# FitnessTracker.net
KiCad netlist of a schematic drawn in EAGLE
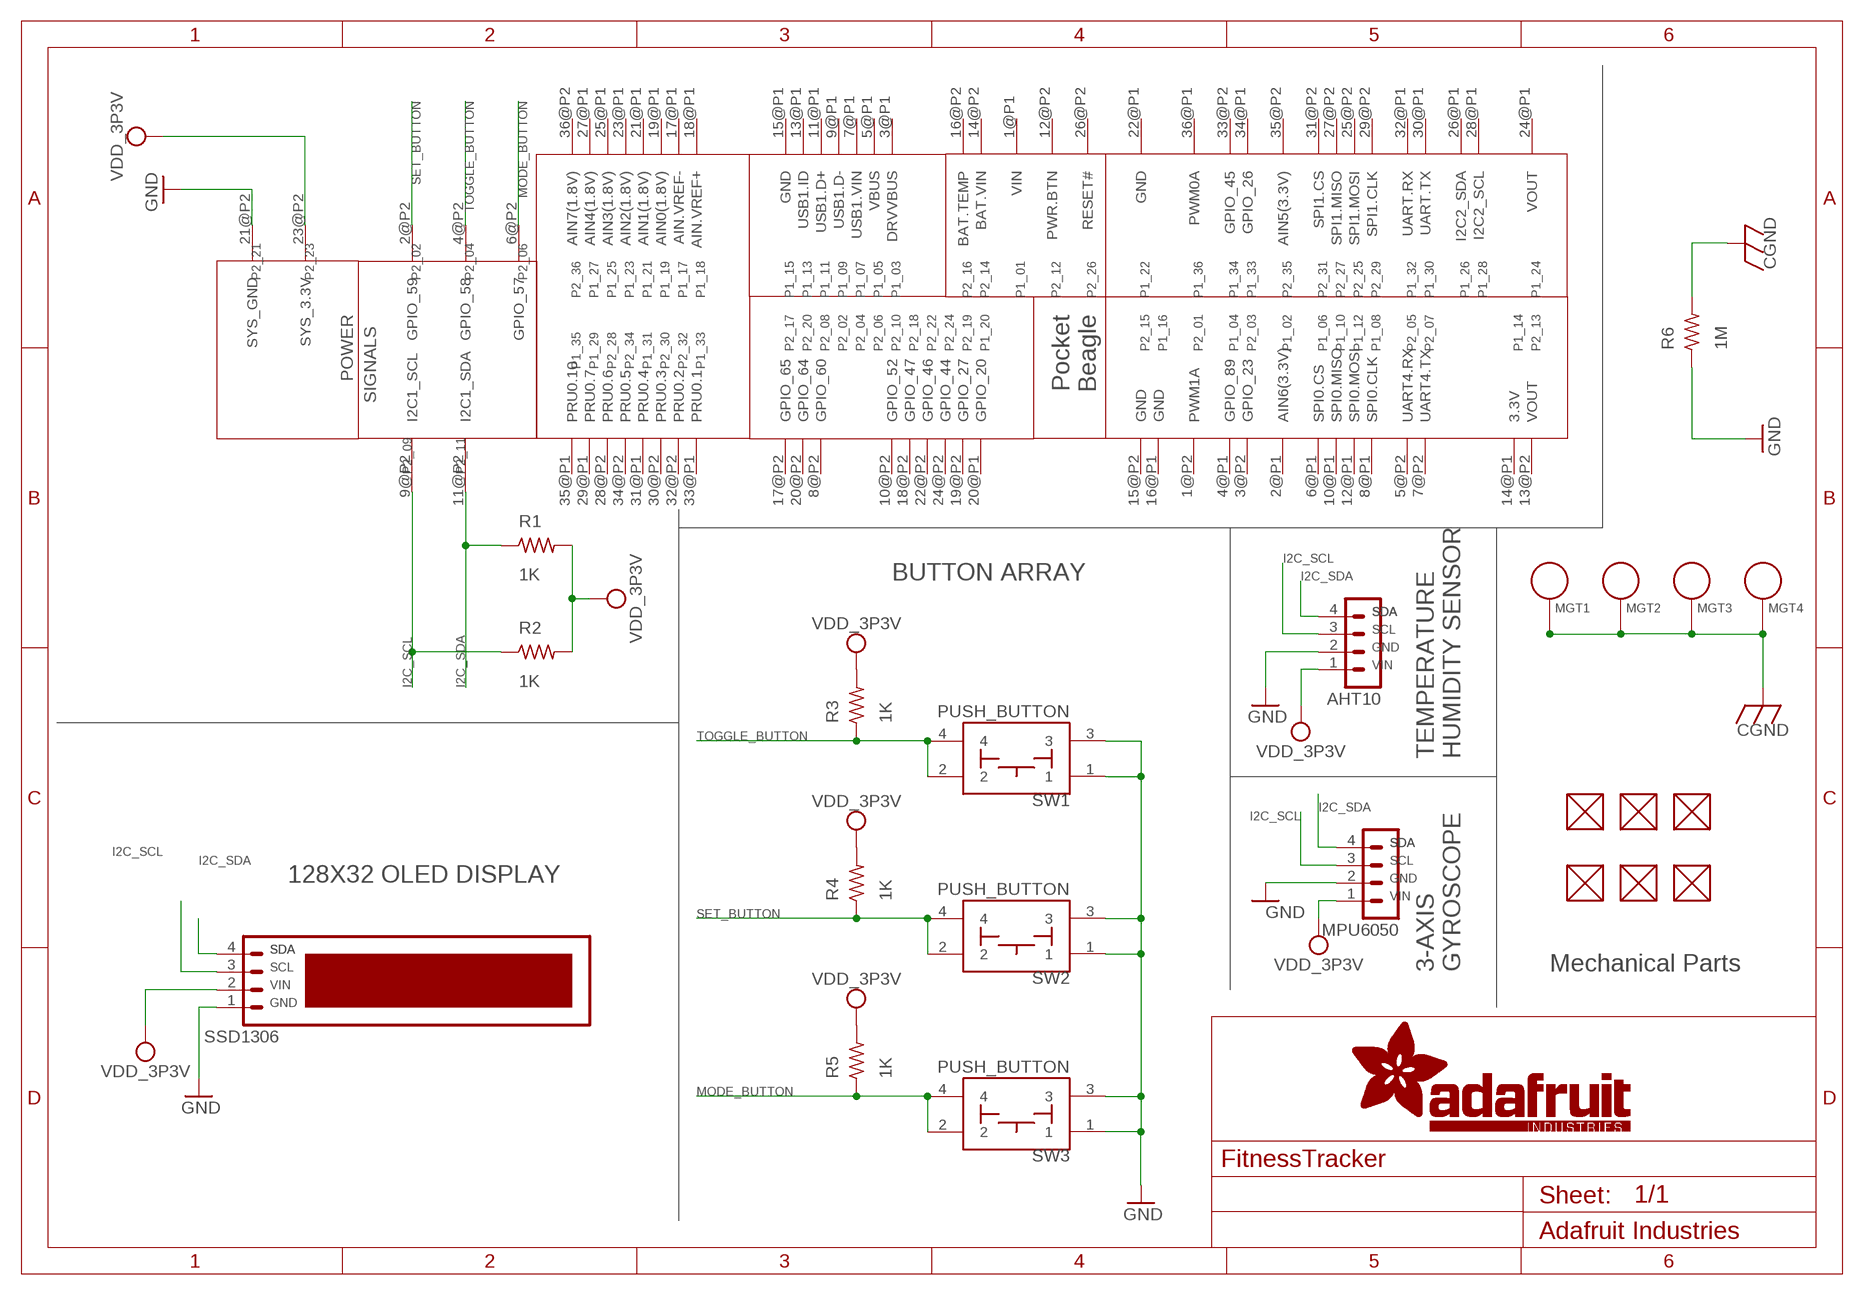
[diagram p0: schematic, sheet 1]

(export (version "E")
  (design (tool "Eeschema 10.0.6"))
  (components
    (comp (ref "FUD1")
      (value "FIDUCIAL")
      (footprint "eagle-import:FIDUCIAL_40MIL")
      (libsource (lib "eagle-import") (part "FIDUCIAL"))
    )
    (comp (ref "FUD2")
      (value "FIDUCIAL")
      (footprint "eagle-import:FIDUCIAL_40MIL")
      (libsource (lib "eagle-import") (part "FIDUCIAL"))
    )
    (comp (ref "FUD3")
      (value "FIDUCIAL")
      (footprint "eagle-import:FIDUCIAL_40MIL")
      (libsource (lib "eagle-import") (part "FIDUCIAL"))
    )
    (comp (ref "FUD4")
      (value "FIDUCIAL")
      (footprint "eagle-import:FIDUCIAL_40MIL")
      (libsource (lib "eagle-import") (part "FIDUCIAL"))
    )
    (comp (ref "FUD5")
      (value "FIDUCIAL")
      (footprint "eagle-import:FIDUCIAL_40MIL")
      (libsource (lib "eagle-import") (part "FIDUCIAL"))
    )
    (comp (ref "FUD6")
      (value "FIDUCIAL")
      (footprint "eagle-import:FIDUCIAL_40MIL")
      (libsource (lib "eagle-import") (part "FIDUCIAL"))
    )
    (comp (ref "MGT1")
      (value "MOUNTING_HOLE")
      (footprint "eagle-import:MOUNTING_HOLE")
      (libsource (lib "eagle-import") (part "MOUNTING_HOLE"))
    )
    (comp (ref "MGT2")
      (value "MOUNTING_HOLE")
      (footprint "eagle-import:MOUNTING_HOLE")
      (libsource (lib "eagle-import") (part "MOUNTING_HOLE"))
    )
    (comp (ref "MGT3")
      (value "MOUNTING_HOLE")
      (footprint "eagle-import:MOUNTING_HOLE")
      (libsource (lib "eagle-import") (part "MOUNTING_HOLE"))
    )
    (comp (ref "MGT4")
      (value "MOUNTING_HOLE")
      (footprint "eagle-import:MOUNTING_HOLE")
      (libsource (lib "eagle-import") (part "MOUNTING_HOLE"))
    )
    (comp (ref "R1")
      (value "1K")
      (footprint "eagle-import:R0603")
      (libsource (lib "eagle-import") (part "R_R0603"))
    )
    (comp (ref "R2")
      (value "1K")
      (footprint "eagle-import:R0603")
      (libsource (lib "eagle-import") (part "R_R0603"))
    )
    (comp (ref "R3")
      (value "1K")
      (footprint "eagle-import:R0603")
      (libsource (lib "eagle-import") (part "R_R0603"))
    )
    (comp (ref "R4")
      (value "1K")
      (footprint "eagle-import:R0603")
      (libsource (lib "eagle-import") (part "R_R0603"))
    )
    (comp (ref "R5")
      (value "1K")
      (footprint "eagle-import:R0603")
      (libsource (lib "eagle-import") (part "R_R0603"))
    )
    (comp (ref "R6")
      (value "1M")
      (footprint "eagle-import:R0603")
      (libsource (lib "eagle-import") (part "R_R0603"))
    )
    (comp (ref "SW1")
      (value "PUSH_BUTTON")
      (footprint "eagle-import:BUTTON_12.5MM")
      (libsource (lib "eagle-import") (part "PUSH_BUTTON"))
    )
    (comp (ref "SW2")
      (value "PUSH_BUTTON")
      (footprint "eagle-import:BUTTON_12.5MM")
      (libsource (lib "eagle-import") (part "PUSH_BUTTON"))
    )
    (comp (ref "SW3")
      (value "PUSH_BUTTON")
      (footprint "eagle-import:BUTTON_12.5MM")
      (libsource (lib "eagle-import") (part "PUSH_BUTTON"))
    )
    (comp (ref "U$1")
      (value "POCKETBEAGLE")
      (footprint "eagle-import:POCKETBEAGLE")
      (libsource (lib "eagle-import") (part "POCKETBEAGLE"))
    )
    (comp (ref "U$2")
      (value "SSD1306")
      (footprint "eagle-import:MA04-1")
      (libsource (lib "eagle-import") (part "SSD1306"))
    )
    (comp (ref "U$3")
      (value "MPU6050")
      (footprint "eagle-import:MA04-1")
      (libsource (lib "eagle-import") (part "MPU6050"))
    )
    (comp (ref "U$4")
      (value "AHT10")
      (footprint "eagle-import:MA04-1")
      (libsource (lib "eagle-import") (part "AHT10"))
    )
  )
  (nets
    (net (code "1") (name "/I2C_SCL") (class "Default")
      (node (ref "R2") (pin "1") (pinfunction "1_1") (pintype "passive"))
      (node (ref "U$1") (pin "9@P2") (pinfunction "I2C1_SCL_9@P2") (pintype "bidirectional"))
      (node (ref "U$2") (pin "3") (pinfunction "SCL_3") (pintype "passive"))
      (node (ref "U$3") (pin "3") (pinfunction "SCL_3") (pintype "passive"))
      (node (ref "U$4") (pin "3") (pinfunction "SCL_3") (pintype "passive"))
    )
    (net (code "2") (name "/I2C_SDA") (class "Default")
      (node (ref "R1") (pin "1") (pinfunction "1_1") (pintype "passive"))
      (node (ref "U$1") (pin "11@P2") (pinfunction "I2C1_SDA_11@P2") (pintype "bidirectional"))
      (node (ref "U$2") (pin "4") (pinfunction "SDA_4") (pintype "passive"))
      (node (ref "U$3") (pin "4") (pinfunction "SDA_4") (pintype "passive"))
      (node (ref "U$4") (pin "4") (pinfunction "SDA_4") (pintype "passive"))
    )
    (net (code "3") (name "/MODE_BUTTON") (class "Default")
      (node (ref "R5") (pin "1") (pinfunction "1_1") (pintype "passive"))
      (node (ref "SW3") (pin "2") (pinfunction "2_2") (pintype "bidirectional"))
      (node (ref "SW3") (pin "4") (pinfunction "4_4") (pintype "bidirectional"))
      (node (ref "U$1") (pin "6@P2") (pinfunction "GPIO_57_6@P2") (pintype "bidirectional"))
    )
    (net (code "4") (name "/SET_BUTTON") (class "Default")
      (node (ref "R4") (pin "1") (pinfunction "1_1") (pintype "passive"))
      (node (ref "SW2") (pin "2") (pinfunction "2_2") (pintype "bidirectional"))
      (node (ref "SW2") (pin "4") (pinfunction "4_4") (pintype "bidirectional"))
      (node (ref "U$1") (pin "2@P2") (pinfunction "GPIO_59_2@P2") (pintype "bidirectional"))
    )
    (net (code "5") (name "/TOGGLE_BUTTON") (class "Default")
      (node (ref "R3") (pin "1") (pinfunction "1_1") (pintype "passive"))
      (node (ref "SW1") (pin "2") (pinfunction "2_2") (pintype "bidirectional"))
      (node (ref "SW1") (pin "4") (pinfunction "4_4") (pintype "bidirectional"))
      (node (ref "U$1") (pin "4@P2") (pinfunction "GPIO_58_4@P2") (pintype "bidirectional"))
    )
    (net (code "6") (name "CGND") (class "Default")
      (node (ref "MGT1") (pin "P$1") (pinfunction "P$1_P$1") (pintype "bidirectional"))
      (node (ref "MGT2") (pin "P$1") (pinfunction "P$1_P$1") (pintype "bidirectional"))
      (node (ref "MGT3") (pin "P$1") (pinfunction "P$1_P$1") (pintype "bidirectional"))
      (node (ref "MGT4") (pin "P$1") (pinfunction "P$1_P$1") (pintype "bidirectional"))
      (node (ref "R6") (pin "2") (pinfunction "2_2") (pintype "passive"))
    )
    (net (code "7") (name "GND") (class "Default")
      (node (ref "R6") (pin "1") (pinfunction "1_1") (pintype "passive"))
      (node (ref "SW1") (pin "1") (pinfunction "1_1") (pintype "bidirectional"))
      (node (ref "SW1") (pin "3") (pinfunction "3_3") (pintype "bidirectional"))
      (node (ref "SW2") (pin "1") (pinfunction "1_1") (pintype "bidirectional"))
      (node (ref "SW2") (pin "3") (pinfunction "3_3") (pintype "bidirectional"))
      (node (ref "SW3") (pin "1") (pinfunction "1_1") (pintype "bidirectional"))
      (node (ref "SW3") (pin "3") (pinfunction "3_3") (pintype "bidirectional"))
      (node (ref "U$1") (pin "21@P2") (pinfunction "SYS_GND_21@P2") (pintype "power_in"))
      (node (ref "U$2") (pin "1") (pinfunction "GND_1") (pintype "passive"))
      (node (ref "U$3") (pin "2") (pinfunction "GND_2") (pintype "passive"))
      (node (ref "U$4") (pin "2") (pinfunction "GND_2") (pintype "passive"))
    )
    (net (code "8") (name "VDD_3P3V") (class "Default")
      (node (ref "R1") (pin "2") (pinfunction "2_2") (pintype "passive"))
      (node (ref "R2") (pin "2") (pinfunction "2_2") (pintype "passive"))
      (node (ref "R3") (pin "2") (pinfunction "2_2") (pintype "passive"))
      (node (ref "R4") (pin "2") (pinfunction "2_2") (pintype "passive"))
      (node (ref "R5") (pin "2") (pinfunction "2_2") (pintype "passive"))
      (node (ref "U$1") (pin "23@P2") (pinfunction "SYS_3.3V_23@P2") (pintype "power_in"))
      (node (ref "U$2") (pin "2") (pinfunction "VIN_2") (pintype "passive"))
      (node (ref "U$3") (pin "1") (pinfunction "VIN_1") (pintype "passive"))
      (node (ref "U$4") (pin "1") (pinfunction "VIN_1") (pintype "passive"))
    )
    (net (code "9") (name "unconnected-(FUD1-PadP$1)") (class "Default")
      (node (ref "FUD1") (pin "P$1") (pinfunction "P$1_P$1") (pintype "no_connect"))
    )
    (net (code "10") (name "unconnected-(FUD2-PadP$1)") (class "Default")
      (node (ref "FUD2") (pin "P$1") (pinfunction "P$1_P$1") (pintype "no_connect"))
    )
    (net (code "11") (name "unconnected-(FUD3-PadP$1)") (class "Default")
      (node (ref "FUD3") (pin "P$1") (pinfunction "P$1_P$1") (pintype "no_connect"))
    )
    (net (code "12") (name "unconnected-(FUD4-PadP$1)") (class "Default")
      (node (ref "FUD4") (pin "P$1") (pinfunction "P$1_P$1") (pintype "no_connect"))
    )
    (net (code "13") (name "unconnected-(FUD5-PadP$1)") (class "Default")
      (node (ref "FUD5") (pin "P$1") (pinfunction "P$1_P$1") (pintype "no_connect"))
    )
    (net (code "14") (name "unconnected-(FUD6-PadP$1)") (class "Default")
      (node (ref "FUD6") (pin "P$1") (pinfunction "P$1_P$1") (pintype "no_connect"))
    )
    (net (code "15") (name "unconnected-(U$1A-3.3V-Pad14@P1)") (class "Default")
      (node (ref "U$1") (pin "14@P1") (pinfunction "3.3V_14@P1") (pintype "bidirectional"))
    )
    (net (code "16") (name "unconnected-(U$1A-AIN.VREF+-Pad18@P1)") (class "Default")
      (node (ref "U$1") (pin "18@P1") (pinfunction "AIN.VREF+_18@P1") (pintype "bidirectional"))
    )
    (net (code "17") (name "unconnected-(U$1A-AIN.VREF--Pad17@P1)") (class "Default")
      (node (ref "U$1") (pin "17@P1") (pinfunction "AIN.VREF-_17@P1") (pintype "bidirectional"))
    )
    (net (code "18") (name "unconnected-(U$1A-AIN0(1.8V)-Pad19@P1)") (class "Default")
      (node (ref "U$1") (pin "19@P1") (pinfunction "AIN0(1.8V)_19@P1") (pintype "bidirectional"))
    )
    (net (code "19") (name "unconnected-(U$1A-AIN1(1.8V)-Pad21@P1)") (class "Default")
      (node (ref "U$1") (pin "21@P1") (pinfunction "AIN1(1.8V)_21@P1") (pintype "bidirectional"))
    )
    (net (code "20") (name "unconnected-(U$1A-AIN2(1.8V)-Pad23@P1)") (class "Default")
      (node (ref "U$1") (pin "23@P1") (pinfunction "AIN2(1.8V)_23@P1") (pintype "bidirectional"))
    )
    (net (code "21") (name "unconnected-(U$1A-AIN3(1.8V)-Pad25@P1)") (class "Default")
      (node (ref "U$1") (pin "25@P1") (pinfunction "AIN3(1.8V)_25@P1") (pintype "bidirectional"))
    )
    (net (code "22") (name "unconnected-(U$1A-AIN4(1.8V)-Pad27@P1)") (class "Default")
      (node (ref "U$1") (pin "27@P1") (pinfunction "AIN4(1.8V)_27@P1") (pintype "bidirectional"))
    )
    (net (code "23") (name "unconnected-(U$1A-AIN5(3.3V)-Pad35@P2)") (class "Default")
      (node (ref "U$1") (pin "35@P2") (pinfunction "AIN5(3.3V)_35@P2") (pintype "bidirectional"))
    )
    (net (code "24") (name "unconnected-(U$1A-AIN6(3.3V)-Pad2@P1)") (class "Default")
      (node (ref "U$1") (pin "2@P1") (pinfunction "AIN6(3.3V)_2@P1") (pintype "bidirectional"))
    )
    (net (code "25") (name "unconnected-(U$1A-AIN7(1.8V)-Pad36@P2)") (class "Default")
      (node (ref "U$1") (pin "36@P2") (pinfunction "AIN7(1.8V)_36@P2") (pintype "bidirectional"))
    )
    (net (code "26") (name "unconnected-(U$1A-BAT.TEMP-Pad16@P2)") (class "Default")
      (node (ref "U$1") (pin "16@P2") (pinfunction "BAT.TEMP_16@P2") (pintype "bidirectional"))
    )
    (net (code "27") (name "unconnected-(U$1A-BAT.VIN-Pad14@P2)") (class "Default")
      (node (ref "U$1") (pin "14@P2") (pinfunction "BAT.VIN_14@P2") (pintype "bidirectional"))
    )
    (net (code "28") (name "unconnected-(U$1A-DRVVBUS-Pad3@P1)") (class "Default")
      (node (ref "U$1") (pin "3@P1") (pinfunction "DRVVBUS_3@P1") (pintype "bidirectional"))
    )
    (net (code "29") (name "unconnected-(U$1A-GND-Pad15@P1)") (class "Default")
      (node (ref "U$1") (pin "15@P1") (pinfunction "GND_15@P1") (pintype "bidirectional"))
    )
    (net (code "30") (name "unconnected-(U$1A-GND-Pad15@P2)") (class "Default")
      (node (ref "U$1") (pin "15@P2") (pinfunction "GND_15@P2") (pintype "bidirectional"))
    )
    (net (code "31") (name "unconnected-(U$1A-GND-Pad16@P1)") (class "Default")
      (node (ref "U$1") (pin "16@P1") (pinfunction "GND_16@P1") (pintype "bidirectional"))
    )
    (net (code "32") (name "unconnected-(U$1A-GND-Pad22@P1)") (class "Default")
      (node (ref "U$1") (pin "22@P1") (pinfunction "GND_22@P1") (pintype "bidirectional"))
    )
    (net (code "33") (name "unconnected-(U$1A-GPIO_20-Pad20@P1)") (class "Default")
      (node (ref "U$1") (pin "20@P1") (pinfunction "GPIO_20_20@P1") (pintype "bidirectional"))
    )
    (net (code "34") (name "unconnected-(U$1A-GPIO_23-Pad3@P2)") (class "Default")
      (node (ref "U$1") (pin "3@P2") (pinfunction "GPIO_23_3@P2") (pintype "bidirectional"))
    )
    (net (code "35") (name "unconnected-(U$1A-GPIO_26-Pad34@P1)") (class "Default")
      (node (ref "U$1") (pin "34@P1") (pinfunction "GPIO_26_34@P1") (pintype "bidirectional"))
    )
    (net (code "36") (name "unconnected-(U$1A-GPIO_27-Pad19@P2)") (class "Default")
      (node (ref "U$1") (pin "19@P2") (pinfunction "GPIO_27_19@P2") (pintype "bidirectional"))
    )
    (net (code "37") (name "unconnected-(U$1A-GPIO_44-Pad24@P2)") (class "Default")
      (node (ref "U$1") (pin "24@P2") (pinfunction "GPIO_44_24@P2") (pintype "bidirectional"))
    )
    (net (code "38") (name "unconnected-(U$1A-GPIO_45-Pad33@P2)") (class "Default")
      (node (ref "U$1") (pin "33@P2") (pinfunction "GPIO_45_33@P2") (pintype "bidirectional"))
    )
    (net (code "39") (name "unconnected-(U$1A-GPIO_46-Pad22@P2)") (class "Default")
      (node (ref "U$1") (pin "22@P2") (pinfunction "GPIO_46_22@P2") (pintype "bidirectional"))
    )
    (net (code "40") (name "unconnected-(U$1A-GPIO_47-Pad18@P2)") (class "Default")
      (node (ref "U$1") (pin "18@P2") (pinfunction "GPIO_47_18@P2") (pintype "bidirectional"))
    )
    (net (code "41") (name "unconnected-(U$1A-GPIO_52-Pad10@P2)") (class "Default")
      (node (ref "U$1") (pin "10@P2") (pinfunction "GPIO_52_10@P2") (pintype "bidirectional"))
    )
    (net (code "42") (name "unconnected-(U$1A-GPIO_60-Pad8@P2)") (class "Default")
      (node (ref "U$1") (pin "8@P2") (pinfunction "GPIO_60_8@P2") (pintype "bidirectional"))
    )
    (net (code "43") (name "unconnected-(U$1A-GPIO_64-Pad20@P2)") (class "Default")
      (node (ref "U$1") (pin "20@P2") (pinfunction "GPIO_64_20@P2") (pintype "bidirectional"))
    )
    (net (code "44") (name "unconnected-(U$1A-GPIO_65-Pad17@P2)") (class "Default")
      (node (ref "U$1") (pin "17@P2") (pinfunction "GPIO_65_17@P2") (pintype "bidirectional"))
    )
    (net (code "45") (name "unconnected-(U$1A-GPIO_89-Pad4@P1)") (class "Default")
      (node (ref "U$1") (pin "4@P1") (pinfunction "GPIO_89_4@P1") (pintype "bidirectional"))
    )
    (net (code "46") (name "unconnected-(U$1A-I2C2_SCL-Pad28@P1)") (class "Default")
      (node (ref "U$1") (pin "28@P1") (pinfunction "I2C2_SCL_28@P1") (pintype "bidirectional"))
    )
    (net (code "47") (name "unconnected-(U$1A-I2C2_SDA-Pad26@P1)") (class "Default")
      (node (ref "U$1") (pin "26@P1") (pinfunction "I2C2_SDA_26@P1") (pintype "bidirectional"))
    )
    (net (code "48") (name "unconnected-(U$1A-PRU0.1-Pad33@P1)") (class "Default")
      (node (ref "U$1") (pin "33@P1") (pinfunction "PRU0.1_33@P1") (pintype "bidirectional"))
    )
    (net (code "49") (name "unconnected-(U$1A-PRU0.2-Pad32@P2)") (class "Default")
      (node (ref "U$1") (pin "32@P2") (pinfunction "PRU0.2_32@P2") (pintype "bidirectional"))
    )
    (net (code "50") (name "unconnected-(U$1A-PRU0.3-Pad30@P2)") (class "Default")
      (node (ref "U$1") (pin "30@P2") (pinfunction "PRU0.3_30@P2") (pintype "bidirectional"))
    )
    (net (code "51") (name "unconnected-(U$1A-PRU0.4-Pad31@P1)") (class "Default")
      (node (ref "U$1") (pin "31@P1") (pinfunction "PRU0.4_31@P1") (pintype "bidirectional"))
    )
    (net (code "52") (name "unconnected-(U$1A-PRU0.5-Pad34@P2)") (class "Default")
      (node (ref "U$1") (pin "34@P2") (pinfunction "PRU0.5_34@P2") (pintype "bidirectional"))
    )
    (net (code "53") (name "unconnected-(U$1A-PRU0.6-Pad28@P2)") (class "Default")
      (node (ref "U$1") (pin "28@P2") (pinfunction "PRU0.6_28@P2") (pintype "bidirectional"))
    )
    (net (code "54") (name "unconnected-(U$1A-PRU0.7-Pad29@P1)") (class "Default")
      (node (ref "U$1") (pin "29@P1") (pinfunction "PRU0.7_29@P1") (pintype "bidirectional"))
    )
    (net (code "55") (name "unconnected-(U$1A-PRU0.10-Pad35@P1)") (class "Default")
      (node (ref "U$1") (pin "35@P1") (pinfunction "PRU0.10_35@P1") (pintype "bidirectional"))
    )
    (net (code "56") (name "unconnected-(U$1A-PWM0A-Pad36@P1)") (class "Default")
      (node (ref "U$1") (pin "36@P1") (pinfunction "PWM0A_36@P1") (pintype "bidirectional"))
    )
    (net (code "57") (name "unconnected-(U$1A-PWM1A-Pad1@P2)") (class "Default")
      (node (ref "U$1") (pin "1@P2") (pinfunction "PWM1A_1@P2") (pintype "bidirectional"))
    )
    (net (code "58") (name "unconnected-(U$1A-PWR.BTN-Pad12@P2)") (class "Default")
      (node (ref "U$1") (pin "12@P2") (pinfunction "PWR.BTN_12@P2") (pintype "bidirectional"))
    )
    (net (code "59") (name "unconnected-(U$1A-RESET#-Pad26@P2)") (class "Default")
      (node (ref "U$1") (pin "26@P2") (pinfunction "RESET#_26@P2") (pintype "bidirectional"))
    )
    (net (code "60") (name "unconnected-(U$1A-SPI0.CLK-Pad8@P1)") (class "Default")
      (node (ref "U$1") (pin "8@P1") (pinfunction "SPI0.CLK_8@P1") (pintype "bidirectional"))
    )
    (net (code "61") (name "unconnected-(U$1A-SPI0.CS-Pad6@P1)") (class "Default")
      (node (ref "U$1") (pin "6@P1") (pinfunction "SPI0.CS_6@P1") (pintype "bidirectional"))
    )
    (net (code "62") (name "unconnected-(U$1A-SPI0.MISO-Pad10@P1)") (class "Default")
      (node (ref "U$1") (pin "10@P1") (pinfunction "SPI0.MISO_10@P1") (pintype "bidirectional"))
    )
    (net (code "63") (name "unconnected-(U$1A-SPI0.MOSI-Pad12@P1)") (class "Default")
      (node (ref "U$1") (pin "12@P1") (pinfunction "SPI0.MOSI_12@P1") (pintype "bidirectional"))
    )
    (net (code "64") (name "unconnected-(U$1A-SPI1.CLK-Pad29@P2)") (class "Default")
      (node (ref "U$1") (pin "29@P2") (pinfunction "SPI1.CLK_29@P2") (pintype "bidirectional"))
    )
    (net (code "65") (name "unconnected-(U$1A-SPI1.CS-Pad31@P2)") (class "Default")
      (node (ref "U$1") (pin "31@P2") (pinfunction "SPI1.CS_31@P2") (pintype "bidirectional"))
    )
    (net (code "66") (name "unconnected-(U$1A-SPI1.MISO-Pad27@P2)") (class "Default")
      (node (ref "U$1") (pin "27@P2") (pinfunction "SPI1.MISO_27@P2") (pintype "bidirectional"))
    )
    (net (code "67") (name "unconnected-(U$1A-SPI1.MOSI-Pad25@P2)") (class "Default")
      (node (ref "U$1") (pin "25@P2") (pinfunction "SPI1.MOSI_25@P2") (pintype "bidirectional"))
    )
    (net (code "68") (name "unconnected-(U$1A-UART.RX-Pad32@P1)") (class "Default")
      (node (ref "U$1") (pin "32@P1") (pinfunction "UART.RX_32@P1") (pintype "bidirectional"))
    )
    (net (code "69") (name "unconnected-(U$1A-UART.TX-Pad30@P1)") (class "Default")
      (node (ref "U$1") (pin "30@P1") (pinfunction "UART.TX_30@P1") (pintype "bidirectional"))
    )
    (net (code "70") (name "unconnected-(U$1A-UART4.RX-Pad5@P2)") (class "Default")
      (node (ref "U$1") (pin "5@P2") (pinfunction "UART4.RX_5@P2") (pintype "bidirectional"))
    )
    (net (code "71") (name "unconnected-(U$1A-UART4.TX-Pad7@P2)") (class "Default")
      (node (ref "U$1") (pin "7@P2") (pinfunction "UART4.TX_7@P2") (pintype "bidirectional"))
    )
    (net (code "72") (name "unconnected-(U$1A-USB1.D+-Pad11@P1)") (class "Default")
      (node (ref "U$1") (pin "11@P1") (pinfunction "USB1.D+_11@P1") (pintype "bidirectional"))
    )
    (net (code "73") (name "unconnected-(U$1A-USB1.D--Pad9@P1)") (class "Default")
      (node (ref "U$1") (pin "9@P1") (pinfunction "USB1.D-_9@P1") (pintype "bidirectional"))
    )
    (net (code "74") (name "unconnected-(U$1A-USB1.ID-Pad13@P1)") (class "Default")
      (node (ref "U$1") (pin "13@P1") (pinfunction "USB1.ID_13@P1") (pintype "bidirectional"))
    )
    (net (code "75") (name "unconnected-(U$1A-USB1.VIN-Pad7@P1)") (class "Default")
      (node (ref "U$1") (pin "7@P1") (pinfunction "USB1.VIN_7@P1") (pintype "bidirectional"))
    )
    (net (code "76") (name "unconnected-(U$1A-VBUS-Pad5@P1)") (class "Default")
      (node (ref "U$1") (pin "5@P1") (pinfunction "VBUS_5@P1") (pintype "bidirectional"))
    )
    (net (code "77") (name "unconnected-(U$1A-VIN-Pad1@P1)") (class "Default")
      (node (ref "U$1") (pin "1@P1") (pinfunction "VIN_1@P1") (pintype "bidirectional"))
    )
    (net (code "78") (name "unconnected-(U$1A-VOUT-Pad13@P2)") (class "Default")
      (node (ref "U$1") (pin "13@P2") (pinfunction "VOUT_13@P2") (pintype "bidirectional"))
    )
    (net (code "79") (name "unconnected-(U$1A-VOUT-Pad24@P1)") (class "Default")
      (node (ref "U$1") (pin "24@P1") (pinfunction "VOUT_24@P1") (pintype "bidirectional"))
    )
  )
)
